# Micro.net
KiCad netlist of a schematic drawn in Altium Designer
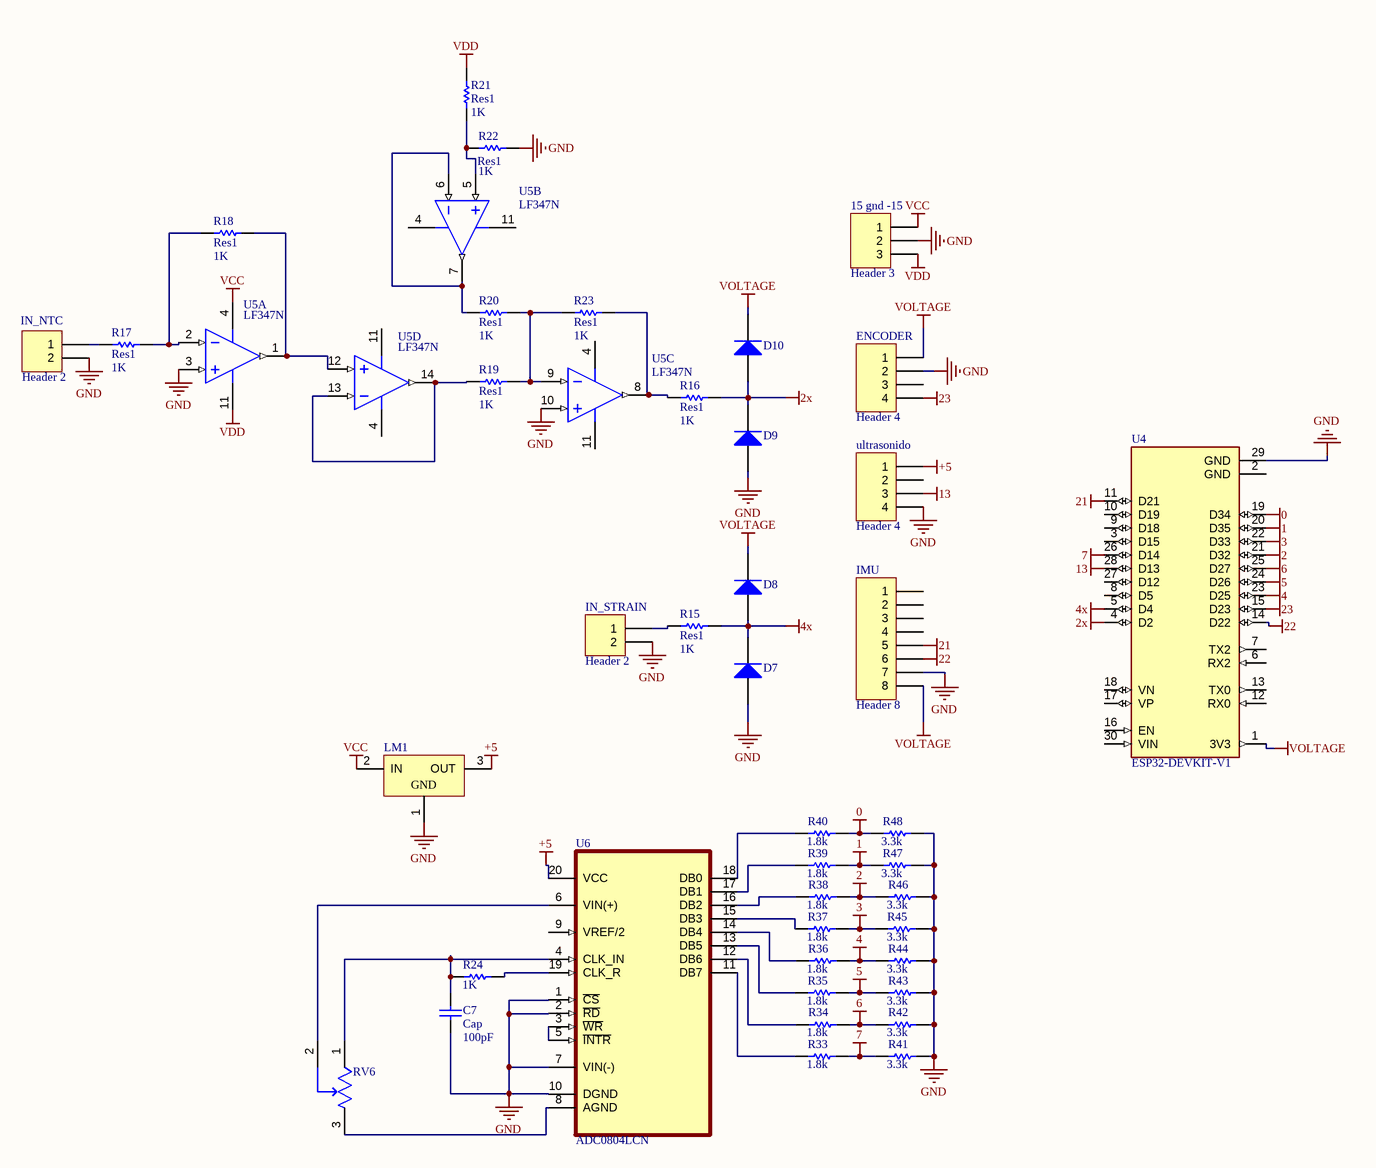
[diagram p0: Micro.SchDoc]

(export (version "E")
  (design (tool "Eeschema 10.0.6"))
  (components
    (comp (ref "15 gnd -15")
      (value "Header 3")
      (footprint "HDR1X3")
      (description "Header, 3-Pin")
      (fields (field (name "PUBLISHER") "Altium Limited"))
      (libsource (lib "Miscellaneous Connectors") (part "Header 3"))
    )
    (comp (ref "C7")
      (value "Cap")
      (footprint "RAD-0.3")
      (description "Capacitor")
      (fields (field (name "ALTIUM_VALUE") "100pF") (field (name "PUBLISHER") "Altium Limited"))
      (libsource (lib "Miscellaneous Devices") (part "Cap"))
    )
    (comp (ref "D7")
      (value "Diode 1N4004")
      (footprint "DO-41")
      (description "1 Amp General Purpose Rectifier")
      (fields (field (name "PUBLISHER") "Altium Limited"))
      (libsource (lib "Miscellaneous Devices") (part "Diode 1N4004"))
    )
    (comp (ref "D8")
      (value "Diode 1N4004")
      (footprint "DO-41")
      (description "1 Amp General Purpose Rectifier")
      (fields (field (name "PUBLISHER") "Altium Limited"))
      (libsource (lib "Miscellaneous Devices") (part "Diode 1N4004"))
    )
    (comp (ref "D9")
      (value "Diode 1N4004")
      (footprint "DO-41")
      (description "1 Amp General Purpose Rectifier")
      (fields (field (name "PUBLISHER") "Altium Limited"))
      (libsource (lib "Miscellaneous Devices") (part "Diode 1N4004"))
    )
    (comp (ref "D10")
      (value "Diode 1N4004")
      (footprint "DO-41")
      (description "1 Amp General Purpose Rectifier")
      (fields (field (name "PUBLISHER") "Altium Limited"))
      (libsource (lib "Miscellaneous Devices") (part "Diode 1N4004"))
    )
    (comp (ref "ENCODER")
      (value "Header 4")
      (footprint "HDR1X4")
      (description "Header, 4-Pin")
      (fields (field (name "PUBLISHER") "Altium Limited"))
      (libsource (lib "Miscellaneous Connectors") (part "Header 4"))
    )
    (comp (ref "IMU")
      (value "Header 8")
      (footprint "HDR1X8")
      (description "Header, 8-Pin")
      (fields (field (name "PUBLISHER") "Altium Limited"))
      (libsource (lib "Miscellaneous Connectors") (part "Header 8"))
    )
    (comp (ref "IN_NTC")
      (value "Header 2")
      (footprint "HDR1X2")
      (description "Header, 2-Pin")
      (fields (field (name "PUBLISHER") "Altium Limited"))
      (libsource (lib "Miscellaneous Connectors") (part "Header 2"))
    )
    (comp (ref "IN_STRAIN")
      (value "Header 2")
      (footprint "HDR1X2")
      (description "Header, 2-Pin")
      (fields (field (name "PUBLISHER") "Altium Limited"))
      (libsource (lib "Miscellaneous Connectors") (part "Header 2"))
    )
    (comp (ref "LM1")
      (value "LM7905CT/NOPB")
      (footprint "NDE0003A")
      (description "3-Terminal Negative Regulator, 3-pin TO-220, Pb-Free")
      (fields (field (name "MANUFACTURER") "Texas Instruments"))
      (libsource (lib "Altium Content Vault") (part "PM-REG-LM7905-SIL3"))
    )
    (comp (ref "R15")
      (value "Res1")
      (footprint "AXIAL-0.3")
      (description "Resistor")
      (fields (field (name "ALTIUM_VALUE") "1K") (field (name "PUBLISHER") "Altium Limited"))
      (libsource (lib "Miscellaneous Devices") (part "Res1"))
    )
    (comp (ref "R16")
      (value "Res1")
      (footprint "AXIAL-0.3")
      (description "Resistor")
      (fields (field (name "ALTIUM_VALUE") "1K") (field (name "PUBLISHER") "Altium Limited"))
      (libsource (lib "Miscellaneous Devices") (part "Res1"))
    )
    (comp (ref "R17")
      (value "Res1")
      (footprint "AXIAL-0.3")
      (description "Resistor")
      (fields (field (name "ALTIUM_VALUE") "1K") (field (name "PUBLISHER") "Altium Limited"))
      (libsource (lib "Miscellaneous Devices") (part "Res1"))
    )
    (comp (ref "R18")
      (value "Res1")
      (footprint "AXIAL-0.3")
      (description "Resistor")
      (fields (field (name "ALTIUM_VALUE") "1K") (field (name "PUBLISHER") "Altium Limited"))
      (libsource (lib "Miscellaneous Devices") (part "Res1"))
    )
    (comp (ref "R19")
      (value "Res1")
      (footprint "AXIAL-0.3")
      (description "Resistor")
      (fields (field (name "ALTIUM_VALUE") "1K") (field (name "PUBLISHER") "Altium Limited"))
      (libsource (lib "Miscellaneous Devices") (part "Res1"))
    )
    (comp (ref "R20")
      (value "Res1")
      (footprint "AXIAL-0.3")
      (description "Resistor")
      (fields (field (name "ALTIUM_VALUE") "1K") (field (name "PUBLISHER") "Altium Limited"))
      (libsource (lib "Miscellaneous Devices") (part "Res1"))
    )
    (comp (ref "R21")
      (value "Res1")
      (footprint "AXIAL-0.3")
      (description "Resistor")
      (fields (field (name "ALTIUM_VALUE") "1K") (field (name "PUBLISHER") "Altium Limited"))
      (libsource (lib "Miscellaneous Devices") (part "Res1"))
    )
    (comp (ref "R22")
      (value "Res1")
      (footprint "AXIAL-0.3")
      (description "Resistor")
      (fields (field (name "ALTIUM_VALUE") "1K") (field (name "PUBLISHER") "Altium Limited"))
      (libsource (lib "Miscellaneous Devices") (part "Res1"))
    )
    (comp (ref "R23")
      (value "Res1")
      (footprint "AXIAL-0.3")
      (description "Resistor")
      (fields (field (name "ALTIUM_VALUE") "1K") (field (name "PUBLISHER") "Altium Limited"))
      (libsource (lib "Miscellaneous Devices") (part "Res1"))
    )
    (comp (ref "R24")
      (value "1K")
      (footprint "AXIAL-0.3")
      (description "Resistor")
      (fields (field (name "Comment") "Res1") (field (name "PUBLISHER") "Altium Limited"))
      (libsource (lib "Miscellaneous Devices") (part "Res1"))
    )
    (comp (ref "R33")
      (value "1.8k")
      (footprint "AXIAL-0.3")
      (description "Resistor")
      (fields (field (name "Comment") "Res1") (field (name "PUBLISHER") "Altium Limited"))
      (libsource (lib "Miscellaneous Devices") (part "Res1"))
    )
    (comp (ref "R34")
      (value "1.8k")
      (footprint "AXIAL-0.3")
      (description "Resistor")
      (fields (field (name "Comment") "Res1") (field (name "PUBLISHER") "Altium Limited"))
      (libsource (lib "Miscellaneous Devices") (part "Res1"))
    )
    (comp (ref "R35")
      (value "1.8k")
      (footprint "AXIAL-0.3")
      (description "Resistor")
      (fields (field (name "Comment") "Res1") (field (name "PUBLISHER") "Altium Limited"))
      (libsource (lib "Miscellaneous Devices") (part "Res1"))
    )
    (comp (ref "R36")
      (value "1.8k")
      (footprint "AXIAL-0.3")
      (description "Resistor")
      (fields (field (name "Comment") "Res1") (field (name "PUBLISHER") "Altium Limited"))
      (libsource (lib "Miscellaneous Devices") (part "Res1"))
    )
    (comp (ref "R37")
      (value "1.8k")
      (footprint "AXIAL-0.3")
      (description "Resistor")
      (fields (field (name "Comment") "Res1") (field (name "PUBLISHER") "Altium Limited"))
      (libsource (lib "Miscellaneous Devices") (part "Res1"))
    )
    (comp (ref "R38")
      (value "1.8k")
      (footprint "AXIAL-0.3")
      (description "Resistor")
      (fields (field (name "Comment") "Res1") (field (name "PUBLISHER") "Altium Limited"))
      (libsource (lib "Miscellaneous Devices") (part "Res1"))
    )
    (comp (ref "R39")
      (value "1.8k")
      (footprint "AXIAL-0.3")
      (description "Resistor")
      (fields (field (name "Comment") "Res1") (field (name "PUBLISHER") "Altium Limited"))
      (libsource (lib "Miscellaneous Devices") (part "Res1"))
    )
    (comp (ref "R40")
      (value "1.8k")
      (footprint "AXIAL-0.3")
      (description "Resistor")
      (fields (field (name "Comment") "Res1") (field (name "PUBLISHER") "Altium Limited"))
      (libsource (lib "Miscellaneous Devices") (part "Res1"))
    )
    (comp (ref "R41")
      (value "3.3k")
      (footprint "AXIAL-0.3")
      (description "Resistor")
      (fields (field (name "Comment") "Res1") (field (name "PUBLISHER") "Altium Limited"))
      (libsource (lib "Miscellaneous Devices") (part "Res1"))
    )
    (comp (ref "R42")
      (value "3.3k")
      (footprint "AXIAL-0.3")
      (description "Resistor")
      (fields (field (name "Comment") "Res1") (field (name "PUBLISHER") "Altium Limited"))
      (libsource (lib "Miscellaneous Devices") (part "Res1"))
    )
    (comp (ref "R43")
      (value "3.3k")
      (footprint "AXIAL-0.3")
      (description "Resistor")
      (fields (field (name "Comment") "Res1") (field (name "PUBLISHER") "Altium Limited"))
      (libsource (lib "Miscellaneous Devices") (part "Res1"))
    )
    (comp (ref "R44")
      (value "3.3k")
      (footprint "AXIAL-0.3")
      (description "Resistor")
      (fields (field (name "Comment") "Res1") (field (name "PUBLISHER") "Altium Limited"))
      (libsource (lib "Miscellaneous Devices") (part "Res1"))
    )
    (comp (ref "R45")
      (value "3.3k")
      (footprint "AXIAL-0.3")
      (description "Resistor")
      (fields (field (name "Comment") "Res1") (field (name "PUBLISHER") "Altium Limited"))
      (libsource (lib "Miscellaneous Devices") (part "Res1"))
    )
    (comp (ref "R46")
      (value "3.3k")
      (footprint "AXIAL-0.3")
      (description "Resistor")
      (fields (field (name "Comment") "Res1") (field (name "PUBLISHER") "Altium Limited"))
      (libsource (lib "Miscellaneous Devices") (part "Res1"))
    )
    (comp (ref "R47")
      (value "3.3k")
      (footprint "AXIAL-0.3")
      (description "Resistor")
      (fields (field (name "Comment") "Res1") (field (name "PUBLISHER") "Altium Limited"))
      (libsource (lib "Miscellaneous Devices") (part "Res1"))
    )
    (comp (ref "R48")
      (value "3.3k")
      (footprint "AXIAL-0.3")
      (description "Resistor")
      (fields (field (name "Comment") "Res1") (field (name "PUBLISHER") "Altium Limited"))
      (libsource (lib "Miscellaneous Devices") (part "Res1"))
    )
    (comp (ref "RV6")
      (value "3296W-1-504LF")
      (footprint "FP-3296W-MFG")
      (description "TRIMMER 500K OHM 0.5W PC PIN TOP")
      (fields
        (field (name "MANUFACTURER") "Bourns")
        (field (name "OCTOPART") "https://octopart.com/3296w-1-504lf-bourns-143884")
      )
      (libsource (lib "Altium Content Vault") (part "8d460c8a6f7ec10b1759d1b9c49aa93"))
    )
    (comp (ref "U4")
      (value "ESP32-DEVKIT-V1")
      (footprint "MODULE_ESP32_DEVKIT_V1")
      (fields (field (name "MF") "Do it"))
      (libsource (lib "ESP32-DEVKIT-V1") (part "ESP32-DEVKIT-V1"))
    )
    (comp (ref "U5")
      (value "LF347N")
      (footprint "N0014A")
      (description "Wide Bandwidth Quad JFET Input Operational Amplifier, 14-pin MDIP")
      (fields (field (name "MANUFACTURER") "Texas Instruments"))
      (libsource (lib "Altium Content Vault") (part "AMP-OPA-LF147-14"))
    )
    (comp (ref "U6")
      (value "ADC0804LCN")
      (footprint "DIP254P762X508-20")
      (description "8 Bit Analog to Digital Converter 1 Input 1 SAR 20-DIP")
      (fields (field (name "MF") "Renesas Electronics"))
      (libsource (lib "ADC0804LCN") (part "ADC0804LCN"))
    )
    (comp (ref "ultrasonido")
      (value "Header 4")
      (footprint "HDR1X4")
      (description "Header, 4-Pin")
      (fields (field (name "PUBLISHER") "Altium Limited"))
      (libsource (lib "Miscellaneous Connectors") (part "Header 4"))
    )
  )
  (nets
    (net (code "1") (name "+5") (class "Default")
      (node (ref "LM1") (pin "3") (pinfunction "OUT_3") (pintype "power_in"))
      (node (ref "U6") (pin "20") (pinfunction "VCC_20") (pintype "power_in"))
      (node (ref "ultrasonido") (pin "1") (pinfunction "1_1") (pintype "passive"))
    )
    (net (code "2") (name "0") (class "Default")
      (node (ref "R40") (pin "2") (pinfunction "2_2") (pintype "passive"))
      (node (ref "R48") (pin "1") (pinfunction "1_1") (pintype "passive"))
      (node (ref "U4") (pin "19") (pinfunction "D34_19") (pintype "bidirectional"))
    )
    (net (code "3") (name "1") (class "Default")
      (node (ref "R39") (pin "2") (pinfunction "2_2") (pintype "passive"))
      (node (ref "R47") (pin "1") (pinfunction "1_1") (pintype "passive"))
      (node (ref "U4") (pin "20") (pinfunction "D35_20") (pintype "bidirectional"))
    )
    (net (code "4") (name "2") (class "Default")
      (node (ref "R38") (pin "2") (pinfunction "2_2") (pintype "passive"))
      (node (ref "R46") (pin "1") (pinfunction "1_1") (pintype "passive"))
      (node (ref "U4") (pin "21") (pinfunction "D32_21") (pintype "bidirectional"))
    )
    (net (code "5") (name "2x") (class "Default")
      (node (ref "D10") (pin "1") (pinfunction "A_1") (pintype "passive"))
      (node (ref "D9") (pin "2") (pinfunction "K_2") (pintype "passive"))
      (node (ref "R16") (pin "2") (pinfunction "2_2") (pintype "passive"))
      (node (ref "U4") (pin "4") (pinfunction "D2_4") (pintype "bidirectional"))
    )
    (net (code "6") (name "3") (class "Default")
      (node (ref "R37") (pin "2") (pinfunction "2_2") (pintype "passive"))
      (node (ref "R45") (pin "1") (pinfunction "1_1") (pintype "passive"))
      (node (ref "U4") (pin "22") (pinfunction "D33_22") (pintype "bidirectional"))
    )
    (net (code "7") (name "4") (class "Default")
      (node (ref "R36") (pin "2") (pinfunction "2_2") (pintype "passive"))
      (node (ref "R44") (pin "1") (pinfunction "1_1") (pintype "passive"))
      (node (ref "U4") (pin "23") (pinfunction "D25_23") (pintype "bidirectional"))
    )
    (net (code "8") (name "4x") (class "Default")
      (node (ref "D7") (pin "2") (pinfunction "K_2") (pintype "passive"))
      (node (ref "D8") (pin "1") (pinfunction "A_1") (pintype "passive"))
      (node (ref "R15") (pin "2") (pinfunction "2_2") (pintype "passive"))
      (node (ref "U4") (pin "5") (pinfunction "D4_5") (pintype "bidirectional"))
    )
    (net (code "9") (name "5") (class "Default")
      (node (ref "R35") (pin "2") (pinfunction "2_2") (pintype "passive"))
      (node (ref "R43") (pin "1") (pinfunction "1_1") (pintype "passive"))
      (node (ref "U4") (pin "24") (pinfunction "D26_24") (pintype "bidirectional"))
    )
    (net (code "10") (name "6") (class "Default")
      (node (ref "R34") (pin "2") (pinfunction "2_2") (pintype "passive"))
      (node (ref "R42") (pin "1") (pinfunction "1_1") (pintype "passive"))
      (node (ref "U4") (pin "25") (pinfunction "D27_25") (pintype "bidirectional"))
    )
    (net (code "11") (name "7") (class "Default")
      (node (ref "R33") (pin "2") (pinfunction "2_2") (pintype "passive"))
      (node (ref "R41") (pin "1") (pinfunction "1_1") (pintype "passive"))
      (node (ref "U4") (pin "26") (pinfunction "D14_26") (pintype "bidirectional"))
    )
    (net (code "12") (name "13") (class "Default")
      (node (ref "U4") (pin "28") (pinfunction "D13_28") (pintype "bidirectional"))
      (node (ref "ultrasonido") (pin "3") (pinfunction "3_3") (pintype "passive"))
    )
    (net (code "13") (name "21") (class "Default")
      (node (ref "IMU") (pin "5") (pinfunction "5_5") (pintype "passive"))
      (node (ref "U4") (pin "11") (pinfunction "D21_11") (pintype "bidirectional"))
    )
    (net (code "14") (name "22") (class "Default")
      (node (ref "IMU") (pin "6") (pinfunction "6_6") (pintype "passive"))
      (node (ref "U4") (pin "14") (pinfunction "D22_14") (pintype "bidirectional"))
    )
    (net (code "15") (name "23") (class "Default")
      (node (ref "ENCODER") (pin "4") (pinfunction "4_4") (pintype "passive"))
      (node (ref "U4") (pin "15") (pinfunction "D23_15") (pintype "bidirectional"))
    )
    (net (code "16") (name "GND") (class "Default")
      (node (ref "15 gnd -15") (pin "2") (pinfunction "2_2") (pintype "passive"))
      (node (ref "C7") (pin "2") (pinfunction "2_2") (pintype "passive"))
      (node (ref "D7") (pin "1") (pinfunction "A_1") (pintype "passive"))
      (node (ref "D9") (pin "1") (pinfunction "A_1") (pintype "passive"))
      (node (ref "ENCODER") (pin "2") (pinfunction "2_2") (pintype "passive"))
      (node (ref "IMU") (pin "7") (pinfunction "7_7") (pintype "passive"))
      (node (ref "IN_NTC") (pin "2") (pinfunction "2_2") (pintype "passive"))
      (node (ref "IN_STRAIN") (pin "2") (pinfunction "2_2") (pintype "passive"))
      (node (ref "LM1") (pin "1") (pinfunction "GND_1") (pintype "power_in"))
      (node (ref "R22") (pin "2") (pinfunction "2_2") (pintype "passive"))
      (node (ref "R41") (pin "2") (pinfunction "2_2") (pintype "passive"))
      (node (ref "R42") (pin "2") (pinfunction "2_2") (pintype "passive"))
      (node (ref "R43") (pin "2") (pinfunction "2_2") (pintype "passive"))
      (node (ref "R44") (pin "2") (pinfunction "2_2") (pintype "passive"))
      (node (ref "R45") (pin "2") (pinfunction "2_2") (pintype "passive"))
      (node (ref "R46") (pin "2") (pinfunction "2_2") (pintype "passive"))
      (node (ref "R47") (pin "2") (pinfunction "2_2") (pintype "passive"))
      (node (ref "R48") (pin "2") (pinfunction "2_2") (pintype "passive"))
      (node (ref "U4") (pin "29") (pinfunction "GND_29") (pintype "power_in"))
      (node (ref "U5") (pin "10") (pinfunction "IN3+_10") (pintype "input"))
      (node (ref "U5") (pin "3") (pinfunction "IN1+_3") (pintype "input"))
      (node (ref "U6") (pin "1") (pinfunction "~{CS}_1") (pintype "input"))
      (node (ref "U6") (pin "10") (pinfunction "DGND_10") (pintype "passive"))
      (node (ref "U6") (pin "2") (pinfunction "~{RD}_2") (pintype "input"))
      (node (ref "U6") (pin "7") (pinfunction "VIN(-)_7") (pintype "power_in"))
      (node (ref "ultrasonido") (pin "4") (pinfunction "4_4") (pintype "passive"))
    )
    (net (code "17") (name "Net-(IN_NTC-Pad1)") (class "Default")
      (node (ref "IN_NTC") (pin "1") (pinfunction "1_1") (pintype "passive"))
      (node (ref "R17") (pin "1") (pinfunction "1_1") (pintype "passive"))
    )
    (net (code "18") (name "Net-(IN_STRAIN-Pad1)") (class "Default")
      (node (ref "IN_STRAIN") (pin "1") (pinfunction "1_1") (pintype "passive"))
      (node (ref "R15") (pin "1") (pinfunction "1_1") (pintype "passive"))
    )
    (net (code "19") (name "Net-(RV6-CCW)") (class "Default")
      (node (ref "C7") (pin "1") (pinfunction "1_1") (pintype "passive"))
      (node (ref "R24") (pin "1") (pinfunction "1_1") (pintype "passive"))
      (node (ref "RV6") (pin "1") (pinfunction "CCW_1") (pintype "passive"))
      (node (ref "U6") (pin "4") (pinfunction "CLK_IN_4") (pintype "input"))
    )
    (net (code "20") (name "Net-(RV6-CW)") (class "Default")
      (node (ref "RV6") (pin "3") (pinfunction "CW_3") (pintype "passive"))
      (node (ref "U6") (pin "8") (pinfunction "AGND_8") (pintype "passive"))
    )
    (net (code "21") (name "Net-(RV6-WIPER)") (class "Default")
      (node (ref "RV6") (pin "2") (pinfunction "WIPER_2") (pintype "passive"))
      (node (ref "U6") (pin "6") (pinfunction "VIN(+)_6") (pintype "power_in"))
    )
    (net (code "22") (name "Net-(U5A-IN1-)") (class "Default")
      (node (ref "R17") (pin "2") (pinfunction "2_2") (pintype "passive"))
      (node (ref "R18") (pin "1") (pinfunction "1_1") (pintype "passive"))
      (node (ref "U5") (pin "2") (pinfunction "IN1-_2") (pintype "input"))
    )
    (net (code "23") (name "Net-(U5A-OUT1)") (class "Default")
      (node (ref "R18") (pin "2") (pinfunction "2_2") (pintype "passive"))
      (node (ref "U5") (pin "1") (pinfunction "OUT1_1") (pintype "output"))
      (node (ref "U5") (pin "12") (pinfunction "IN4+_12") (pintype "input"))
    )
    (net (code "24") (name "Net-(U5B-IN2+)") (class "Default")
      (node (ref "R21") (pin "1") (pinfunction "1_1") (pintype "passive"))
      (node (ref "R22") (pin "1") (pinfunction "1_1") (pintype "passive"))
      (node (ref "U5") (pin "5") (pinfunction "IN2+_5") (pintype "input"))
    )
    (net (code "25") (name "Net-(U5B-IN2-)") (class "Default")
      (node (ref "R20") (pin "1") (pinfunction "1_1") (pintype "passive"))
      (node (ref "U5") (pin "6") (pinfunction "IN2-_6") (pintype "input"))
      (node (ref "U5") (pin "7") (pinfunction "OUT2_7") (pintype "output"))
    )
    (net (code "26") (name "Net-(U5C-IN3-)") (class "Default")
      (node (ref "R19") (pin "2") (pinfunction "2_2") (pintype "passive"))
      (node (ref "R20") (pin "2") (pinfunction "2_2") (pintype "passive"))
      (node (ref "R23") (pin "1") (pinfunction "1_1") (pintype "passive"))
      (node (ref "U5") (pin "9") (pinfunction "IN3-_9") (pintype "input"))
    )
    (net (code "27") (name "Net-(U5C-OUT3)") (class "Default")
      (node (ref "R16") (pin "1") (pinfunction "1_1") (pintype "passive"))
      (node (ref "R23") (pin "2") (pinfunction "2_2") (pintype "passive"))
      (node (ref "U5") (pin "8") (pinfunction "OUT3_8") (pintype "output"))
    )
    (net (code "28") (name "Net-(U5D-IN4-)") (class "Default")
      (node (ref "R19") (pin "1") (pinfunction "1_1") (pintype "passive"))
      (node (ref "U5") (pin "13") (pinfunction "IN4-_13") (pintype "input"))
      (node (ref "U5") (pin "14") (pinfunction "OUT4_14") (pintype "output"))
    )
    (net (code "29") (name "Net-(U6-CLK_R)") (class "Default")
      (node (ref "R24") (pin "2") (pinfunction "2_2") (pintype "passive"))
      (node (ref "U6") (pin "19") (pinfunction "CLK_R_19") (pintype "input"))
    )
    (net (code "30") (name "Net-(U6-DB0)") (class "Default")
      (node (ref "R40") (pin "1") (pinfunction "1_1") (pintype "passive"))
      (node (ref "U6") (pin "18") (pinfunction "DB0_18") (pintype "passive"))
    )
    (net (code "31") (name "Net-(U6-DB1)") (class "Default")
      (node (ref "R39") (pin "1") (pinfunction "1_1") (pintype "passive"))
      (node (ref "U6") (pin "17") (pinfunction "DB1_17") (pintype "passive"))
    )
    (net (code "32") (name "Net-(U6-DB2)") (class "Default")
      (node (ref "R38") (pin "1") (pinfunction "1_1") (pintype "passive"))
      (node (ref "U6") (pin "16") (pinfunction "DB2_16") (pintype "passive"))
    )
    (net (code "33") (name "Net-(U6-DB3)") (class "Default")
      (node (ref "R37") (pin "1") (pinfunction "1_1") (pintype "passive"))
      (node (ref "U6") (pin "15") (pinfunction "DB3_15") (pintype "passive"))
    )
    (net (code "34") (name "Net-(U6-DB4)") (class "Default")
      (node (ref "R36") (pin "1") (pinfunction "1_1") (pintype "passive"))
      (node (ref "U6") (pin "14") (pinfunction "DB4_14") (pintype "passive"))
    )
    (net (code "35") (name "Net-(U6-DB5)") (class "Default")
      (node (ref "R35") (pin "1") (pinfunction "1_1") (pintype "passive"))
      (node (ref "U6") (pin "13") (pinfunction "DB5_13") (pintype "passive"))
    )
    (net (code "36") (name "Net-(U6-DB6)") (class "Default")
      (node (ref "R34") (pin "1") (pinfunction "1_1") (pintype "passive"))
      (node (ref "U6") (pin "12") (pinfunction "DB6_12") (pintype "passive"))
    )
    (net (code "37") (name "Net-(U6-DB7)") (class "Default")
      (node (ref "R33") (pin "1") (pinfunction "1_1") (pintype "passive"))
      (node (ref "U6") (pin "11") (pinfunction "DB7_11") (pintype "passive"))
    )
    (net (code "38") (name "Net-(U6-~{INTR})") (class "Default")
      (node (ref "U6") (pin "3") (pinfunction "~{WR}_3") (pintype "input"))
      (node (ref "U6") (pin "5") (pinfunction "~{INTR}_5") (pintype "input"))
    )
    (net (code "39") (name "VCC") (class "Default")
      (node (ref "15 gnd -15") (pin "1") (pinfunction "1_1") (pintype "passive"))
      (node (ref "LM1") (pin "2") (pinfunction "IN_2") (pintype "power_in"))
      (node (ref "U5") (pin "4") (pinfunction "V+_4") (pintype "power_in"))
    )
    (net (code "40") (name "VDD") (class "Default")
      (node (ref "15 gnd -15") (pin "3") (pinfunction "3_3") (pintype "passive"))
      (node (ref "R21") (pin "2") (pinfunction "2_2") (pintype "passive"))
      (node (ref "U5") (pin "11") (pinfunction "V-_11") (pintype "power_in"))
    )
    (net (code "41") (name "VOLTAGE") (class "Default")
      (node (ref "D10") (pin "2") (pinfunction "K_2") (pintype "passive"))
      (node (ref "D8") (pin "2") (pinfunction "K_2") (pintype "passive"))
      (node (ref "ENCODER") (pin "1") (pinfunction "1_1") (pintype "passive"))
      (node (ref "IMU") (pin "8") (pinfunction "8_8") (pintype "passive"))
      (node (ref "U4") (pin "1") (pinfunction "3V3_1") (pintype "output"))
    )
    (net (code "42") (name "unconnected-(ENCODER-Pad3)") (class "Default")
      (node (ref "ENCODER") (pin "3") (pinfunction "3_3") (pintype "passive"))
    )
    (net (code "43") (name "unconnected-(IMU-Pad1)") (class "Default")
      (node (ref "IMU") (pin "1") (pinfunction "1_1") (pintype "passive"))
    )
    (net (code "44") (name "unconnected-(IMU-Pad2)") (class "Default")
      (node (ref "IMU") (pin "2") (pinfunction "2_2") (pintype "passive"))
    )
    (net (code "45") (name "unconnected-(IMU-Pad3)") (class "Default")
      (node (ref "IMU") (pin "3") (pinfunction "3_3") (pintype "passive"))
    )
    (net (code "46") (name "unconnected-(IMU-Pad4)") (class "Default")
      (node (ref "IMU") (pin "4") (pinfunction "4_4") (pintype "passive"))
    )
    (net (code "47") (name "unconnected-(U4-D5-Pad8)") (class "Default")
      (node (ref "U4") (pin "8") (pinfunction "D5_8") (pintype "bidirectional"))
    )
    (net (code "48") (name "unconnected-(U4-D12-Pad27)") (class "Default")
      (node (ref "U4") (pin "27") (pinfunction "D12_27") (pintype "bidirectional"))
    )
    (net (code "49") (name "unconnected-(U4-D15-Pad3)") (class "Default")
      (node (ref "U4") (pin "3") (pinfunction "D15_3") (pintype "bidirectional"))
    )
    (net (code "50") (name "unconnected-(U4-D18-Pad9)") (class "Default")
      (node (ref "U4") (pin "9") (pinfunction "D18_9") (pintype "bidirectional"))
    )
    (net (code "51") (name "unconnected-(U4-D19-Pad10)") (class "Default")
      (node (ref "U4") (pin "10") (pinfunction "D19_10") (pintype "bidirectional"))
    )
    (net (code "52") (name "unconnected-(U4-EN-Pad16)") (class "Default")
      (node (ref "U4") (pin "16") (pinfunction "EN_16") (pintype "input"))
    )
    (net (code "53") (name "unconnected-(U4-GND-Pad2)") (class "Default")
      (node (ref "U4") (pin "2") (pinfunction "GND_2") (pintype "power_in"))
    )
    (net (code "54") (name "unconnected-(U4-RX0-Pad12)") (class "Default")
      (node (ref "U4") (pin "12") (pinfunction "RX0_12") (pintype "input"))
    )
    (net (code "55") (name "unconnected-(U4-RX2-Pad6)") (class "Default")
      (node (ref "U4") (pin "6") (pinfunction "RX2_6") (pintype "input"))
    )
    (net (code "56") (name "unconnected-(U4-TX0-Pad13)") (class "Default")
      (node (ref "U4") (pin "13") (pinfunction "TX0_13") (pintype "output"))
    )
    (net (code "57") (name "unconnected-(U4-TX2-Pad7)") (class "Default")
      (node (ref "U4") (pin "7") (pinfunction "TX2_7") (pintype "output"))
    )
    (net (code "58") (name "unconnected-(U4-VIN-Pad30)") (class "Default")
      (node (ref "U4") (pin "30") (pinfunction "VIN_30") (pintype "input"))
    )
    (net (code "59") (name "unconnected-(U4-VN-Pad18)") (class "Default")
      (node (ref "U4") (pin "18") (pinfunction "VN_18") (pintype "bidirectional"))
    )
    (net (code "60") (name "unconnected-(U4-VP-Pad17)") (class "Default")
      (node (ref "U4") (pin "17") (pinfunction "VP_17") (pintype "bidirectional"))
    )
    (net (code "61") (name "unconnected-(U5B-V+-Pad4)") (class "Default")
      (node (ref "U5") (pin "4") (pinfunction "V+_4") (pintype "power_in"))
    )
    (net (code "62") (name "unconnected-(U5B-V--Pad11)") (class "Default")
      (node (ref "U5") (pin "11") (pinfunction "V-_11") (pintype "power_in"))
    )
    (net (code "63") (name "unconnected-(U5C-V+-Pad4)") (class "Default")
      (node (ref "U5") (pin "4") (pinfunction "V+_4") (pintype "power_in"))
    )
    (net (code "64") (name "unconnected-(U5C-V--Pad11)") (class "Default")
      (node (ref "U5") (pin "11") (pinfunction "V-_11") (pintype "power_in"))
    )
    (net (code "65") (name "unconnected-(U5D-V+-Pad4)") (class "Default")
      (node (ref "U5") (pin "4") (pinfunction "V+_4") (pintype "power_in"))
    )
    (net (code "66") (name "unconnected-(U5D-V--Pad11)") (class "Default")
      (node (ref "U5") (pin "11") (pinfunction "V-_11") (pintype "power_in"))
    )
    (net (code "67") (name "unconnected-(U6-VREF{slash}2-Pad9)") (class "Default")
      (node (ref "U6") (pin "9") (pinfunction "VREF/2_9") (pintype "input"))
    )
    (net (code "68") (name "unconnected-(ultrasonido-Pad2)") (class "Default")
      (node (ref "ultrasonido") (pin "2") (pinfunction "2_2") (pintype "passive"))
    )
  )
)
